# Power.net
KiCad netlist of a schematic drawn in Altium Designer
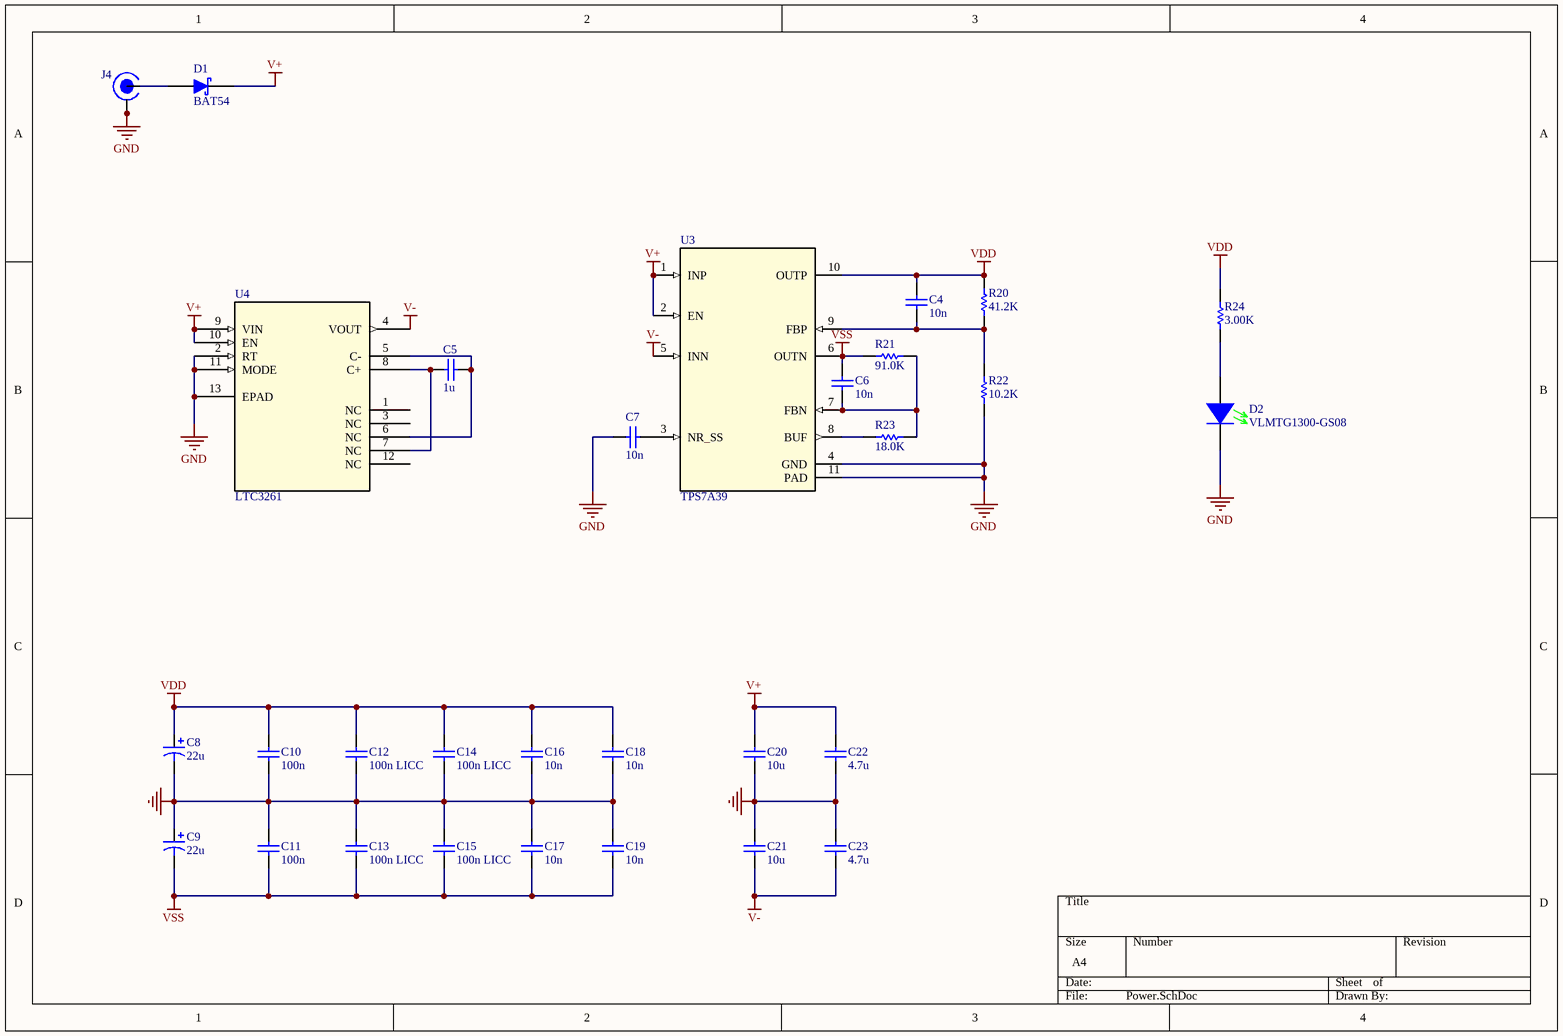
[diagram p0: Power.SchDoc]

(export (version "E")
  (design (tool "Eeschema 10.0.6"))
  (components
    (comp (ref "C4")
      (value "10n")
      (footprint "CAPC0402(1005)50_M")
      (description "CAP CER 10NF±5% 25V C0G 0402")
      (fields
        (field (name "MANUFACTURER") "Murata")
        (field (name "MANUFACTURER PART NUMBER") "GRM1555C1E103JE01D")
      )
      (libsource (lib "Murata GRM 0402") (part "Capacitor_Generic"))
    )
    (comp (ref "C5")
      (value "1u")
      (footprint "CAPC0805(2012)145_M")
      (description "Cap Ceramic 1uF 50V X7R 10% SMD 0805 125C Blister T/R")
      (fields
        (field (name "MANUFACTURER") "Yageo")
        (field (name "MANUFACTURER PART NUMBER") "CC0805KKX7R9BB105")
      )
      (libsource (lib "0805 Caps") (part "CC0805KKX7R9BB105"))
    )
    (comp (ref "C6")
      (value "10n")
      (footprint "CAPC0402(1005)50_M")
      (description "CAP CER 10NF±5% 25V C0G 0402")
      (fields
        (field (name "MANUFACTURER") "Murata")
        (field (name "MANUFACTURER PART NUMBER") "GRM1555C1E103JE01D")
      )
      (libsource (lib "Murata GRM 0402") (part "Capacitor_Generic"))
    )
    (comp (ref "C7")
      (value "10n")
      (footprint "CAPC0402(1005)50_M")
      (description "CAP CER 10NF±5% 25V C0G 0402")
      (fields
        (field (name "MANUFACTURER") "Murata")
        (field (name "MANUFACTURER PART NUMBER") "GRM1555C1E103JE01D")
      )
      (libsource (lib "Murata GRM 0402") (part "Capacitor_Generic"))
    )
    (comp (ref "C8")
      (value "22u")
      (footprint "KEMET D_M")
      (description "CAP TANT 22UF 10% 16V 2917")
      (fields
        (field (name "MANUFACTURER") "KEMET")
        (field (name "MANUFACTURER PART NUMBER") "T491D226K016AT")
      )
      (libsource (lib "Misc Caps") (part "T491D226K016AT"))
    )
    (comp (ref "C9")
      (value "22u")
      (footprint "KEMET D_M")
      (description "CAP TANT 22UF 10% 16V 2917")
      (fields
        (field (name "MANUFACTURER") "KEMET")
        (field (name "MANUFACTURER PART NUMBER") "T491D226K016AT")
      )
      (libsource (lib "Misc Caps") (part "T491D226K016AT"))
    )
    (comp (ref "C10")
      (value "100n")
      (footprint "CAPC0603(1608)100_M")
      (description "CAPACITOR CERAMIC, 0.1UF, 50V, X7R, 10%, 0603")
      (fields
        (field (name "MANUFACTURER") "Yageo")
        (field (name "MANUFACTURER PART NUMBER") "CC0603KRX7R9BB104")
      )
      (libsource (lib "0603 Caps") (part "CC0603KRX7R9BB104"))
    )
    (comp (ref "C11")
      (value "100n")
      (footprint "CAPC0603(1608)100_M")
      (description "CAPACITOR CERAMIC, 0.1UF, 50V, X7R, 10%, 0603")
      (fields
        (field (name "MANUFACTURER") "Yageo")
        (field (name "MANUFACTURER PART NUMBER") "CC0603KRX7R9BB104")
      )
      (libsource (lib "0603 Caps") (part "CC0603KRX7R9BB104"))
    )
    (comp (ref "C12")
      (value "100n LICC")
      (footprint "CAPC0306_M")
      (description "CAP CER 0.1UF 25V X7R 0306")
      (fields
        (field (name "MANUFACTURER") "Taiyo Yuden")
        (field (name "MANUFACTURER PART NUMBER") "TWK107B7104MVHT")
      )
      (libsource (lib "Misc Caps") (part "TWK107B7104MVHT"))
    )
    (comp (ref "C13")
      (value "100n LICC")
      (footprint "CAPC0306_M")
      (description "CAP CER 0.1UF 25V X7R 0306")
      (fields
        (field (name "MANUFACTURER") "Taiyo Yuden")
        (field (name "MANUFACTURER PART NUMBER") "TWK107B7104MVHT")
      )
      (libsource (lib "Misc Caps") (part "TWK107B7104MVHT"))
    )
    (comp (ref "C14")
      (value "100n LICC")
      (footprint "CAPC0306_M")
      (description "CAP CER 0.1UF 25V X7R 0306")
      (fields
        (field (name "MANUFACTURER") "Taiyo Yuden")
        (field (name "MANUFACTURER PART NUMBER") "TWK107B7104MVHT")
      )
      (libsource (lib "Misc Caps") (part "TWK107B7104MVHT"))
    )
    (comp (ref "C15")
      (value "100n LICC")
      (footprint "CAPC0306_M")
      (description "CAP CER 0.1UF 25V X7R 0306")
      (fields
        (field (name "MANUFACTURER") "Taiyo Yuden")
        (field (name "MANUFACTURER PART NUMBER") "TWK107B7104MVHT")
      )
      (libsource (lib "Misc Caps") (part "TWK107B7104MVHT"))
    )
    (comp (ref "C16")
      (value "10n")
      (footprint "CAPC0402(1005)50_M")
      (description "CAP CER 10NF±10% 50V X7R 0402")
      (fields (field (name "PART NUMBER") "GRM155R71H103KA88") (field (name "TOLERANCE") "±10%"))
      (libsource (lib "Murata GRM 0402") (part "Capacitor_Generic"))
    )
    (comp (ref "C17")
      (value "10n")
      (footprint "CAPC0402(1005)50_M")
      (description "CAP CER 10NF±10% 50V X7R 0402")
      (fields (field (name "PART NUMBER") "GRM155R71H103KA88") (field (name "TOLERANCE") "±10%"))
      (libsource (lib "Murata GRM 0402") (part "Capacitor_Generic"))
    )
    (comp (ref "C18")
      (value "10n")
      (footprint "CAPC0402(1005)50_M")
      (description "CAP CER 10NF±10% 50V X7R 0402")
      (fields (field (name "PART NUMBER") "GRM155R71H103KA88") (field (name "TOLERANCE") "±10%"))
      (libsource (lib "Murata GRM 0402") (part "Capacitor_Generic"))
    )
    (comp (ref "C19")
      (value "10n")
      (footprint "CAPC0402(1005)50_M")
      (description "CAP CER 10NF±10% 50V X7R 0402")
      (fields (field (name "PART NUMBER") "GRM155R71H103KA88") (field (name "TOLERANCE") "±10%"))
      (libsource (lib "Murata GRM 0402") (part "Capacitor_Generic"))
    )
    (comp (ref "C20")
      (value "10u")
      (footprint "CAPC1206(3216)170_M")
      (description "CAP CER 10UF 50V X7R 1206")
      (fields
        (field (name "MANUFACTURER") "Samsung")
        (field (name "MANUFACTURER PART NUMBER") "CL31B106KBHNNNE")
      )
      (libsource (lib "Misc Caps") (part "CL31B106KBHNNNE"))
    )
    (comp (ref "C21")
      (value "10u")
      (footprint "CAPC1206(3216)170_M")
      (description "CAP CER 10UF 50V X7R 1206")
      (fields
        (field (name "MANUFACTURER") "Samsung")
        (field (name "MANUFACTURER PART NUMBER") "CL31B106KBHNNNE")
      )
      (libsource (lib "Misc Caps") (part "CL31B106KBHNNNE"))
    )
    (comp (ref "C22")
      (value "4.7u")
      (footprint "CAPC0805(2012)100_M")
      (description "CAP CER 4.7UF 50V X7R 0805")
      (fields
        (field (name "MANUFACTURER") "Murata")
        (field (name "MANUFACTURER PART NUMBER") "GRM21BZ71H475KE15K")
      )
      (libsource (lib "0805 Caps") (part "GRM21BZ71H475KE15K"))
    )
    (comp (ref "C23")
      (value "4.7u")
      (footprint "CAPC0805(2012)100_M")
      (description "CAP CER 4.7UF 50V X7R 0805")
      (fields
        (field (name "MANUFACTURER") "Murata")
        (field (name "MANUFACTURER PART NUMBER") "GRM21BZ71H475KE15K")
      )
      (libsource (lib "0805 Caps") (part "GRM21BZ71H475KE15K"))
    )
    (comp (ref "D1")
      (value "BAT54")
      (footprint "INF-PG-SC59_M")
      (description "DIODE SCHOTTKY 30V 200MA TO236AB")
      (fields
        (field (name "MANUFACTURER") "Nexperia USA")
        (field (name "MANUFACTURER PART NUMBER") "BAT54,215")
      )
      (libsource (lib "Discretes") (part "BAT54"))
    )
    (comp (ref "D2")
      (value "VLMTG1300-GS08")
      (footprint "LED0603(1608)_M")
      (description "LED GREEN 0603 SMD")
      (fields (field (name "MANUFACTURER") "Vishay Semiconductors"))
      (libsource (lib "Discretes") (part "VLMTG1300-GS08"))
    )
    (comp (ref "J4")
      (value "2.1/5.5mm")
      (footprint "CUI PJ-002A")
      (description "CONN PWR JACK 2X5.5MM SOLDER")
      (fields (field (name "MANUFACTURER") "CUI") (field (name "MANUFACTURER PART NUMBER") "PJ-002A"))
      (libsource (lib "Connectors") (part "PJ-002A"))
    )
    (comp (ref "R20")
      (value "41.2K")
      (footprint "RESC0402(1005)_M")
      (description "RES 41.2K OHM 1% 1/16W 0402")
      (fields (field (name "PART NUMBER") "RESC0402-41K2-1pct"))
      (libsource (lib "R0402 - 1pct") (part "Resistor_Generic"))
    )
    (comp (ref "R21")
      (value "91.0K")
      (footprint "RESC0402(1005)_M")
      (description "RES 91.0K OHM 1% 1/16W 0402")
      (fields (field (name "PART NUMBER") "RESC0402-91K0-1pct"))
      (libsource (lib "R0402 - 1pct") (part "Resistor_Generic"))
    )
    (comp (ref "R22")
      (value "10.2K")
      (footprint "RESC0402(1005)_M")
      (description "RES 10.2K OHM 1% 1/16W 0402")
      (fields (field (name "PART NUMBER") "RESC0402-10K2-1pct"))
      (libsource (lib "R0402 - 1pct") (part "Resistor_Generic"))
    )
    (comp (ref "R23")
      (value "18.0K")
      (footprint "RESC0402(1005)_M")
      (description "RES 18.0K OHM 1% 1/16W 0402")
      (fields (field (name "PART NUMBER") "RESC0402-18K0-1pct"))
      (libsource (lib "R0402 - 1pct") (part "Resistor_Generic"))
    )
    (comp (ref "R24")
      (value "3.00K")
      (footprint "RESC0603(1608)_M")
      (description "RES 3.00K OHM 1% 1/10W 0603")
      (fields (field (name "PART NUMBER") "RESC0603-3K00-1pct"))
      (libsource (lib "R0603 - 1pct") (part "Resistor_Generic"))
    )
    (comp (ref "U3")
      (value "TPS7A39")
      (footprint "DSC0010J_NV")
      (description "IC REG LINEAR POS/NEG ADJ 10WSON")
      (fields
        (field (name "MANUFACTURER_PART_NUMBER") "TPS7A3901DSCR")
        (field (name "MANUFACTURER") "Texas Instruments")
        (field (name "COPYRIGHT") "Copyright (C) 2022 Ultra Librarian. All rights reserved.")
      )
      (libsource (lib "IC") (part "TPS7A3901DSCR"))
    )
    (comp (ref "U4")
      (value "LTC3261")
      (footprint "MSOP-12_MSE")
      (description "IC REG CHARG PUMP INV 12MSOP")
      (fields
        (field (name "MANUFACTURER_PART_NUMBER") "ltc3261emse#pbf")
        (field (name "MANUFACTURER") "Analog Devices / Linear Technology")
        (field (name "COPYRIGHT") "Copyright (C) 2022 Ultra Librarian. All rights reserved.")
      )
      (libsource (lib "IC") (part "LTC3261EMSE"))
    )
  )
  (nets
    (net (code "1") (name "GND") (class "Default")
      (node (ref "C10") (pin "2") (pinfunction "2_2") (pintype "passive"))
      (node (ref "C11") (pin "1") (pinfunction "1_1") (pintype "passive"))
      (node (ref "C12") (pin "2") (pinfunction "2_2") (pintype "passive"))
      (node (ref "C13") (pin "1") (pinfunction "1_1") (pintype "passive"))
      (node (ref "C14") (pin "2") (pinfunction "2_2") (pintype "passive"))
      (node (ref "C15") (pin "1") (pinfunction "1_1") (pintype "passive"))
      (node (ref "C16") (pin "2") (pinfunction "2_2") (pintype "passive"))
      (node (ref "C17") (pin "1") (pinfunction "1_1") (pintype "passive"))
      (node (ref "C18") (pin "2") (pinfunction "2_2") (pintype "passive"))
      (node (ref "C19") (pin "1") (pinfunction "1_1") (pintype "passive"))
      (node (ref "C20") (pin "2") (pinfunction "2_2") (pintype "passive"))
      (node (ref "C21") (pin "1") (pinfunction "1_1") (pintype "passive"))
      (node (ref "C22") (pin "2") (pinfunction "2_2") (pintype "passive"))
      (node (ref "C23") (pin "2") (pinfunction "2_2") (pintype "passive"))
      (node (ref "C7") (pin "2") (pinfunction "2_2") (pintype "passive"))
      (node (ref "C8") (pin "2") (pinfunction "2_2") (pintype "passive"))
      (node (ref "C9") (pin "1") (pinfunction "1_1") (pintype "passive"))
      (node (ref "D2") (pin "2") (pinfunction "K_2") (pintype "passive"))
      (node (ref "J4") (pin "2") (pinfunction "2_2") (pintype "passive"))
      (node (ref "J4") (pin "3") (pinfunction "3_3") (pintype "passive"))
      (node (ref "R22") (pin "2") (pinfunction "2_2") (pintype "passive"))
      (node (ref "U3") (pin "11") (pinfunction "PAD_11") (pintype "power_in"))
      (node (ref "U3") (pin "4") (pinfunction "GND_4") (pintype "power_in"))
      (node (ref "U4") (pin "11") (pinfunction "MODE_11") (pintype "input"))
      (node (ref "U4") (pin "13") (pinfunction "EPAD_13") (pintype "passive"))
      (node (ref "U4") (pin "2") (pinfunction "RT_2") (pintype "input"))
    )
    (net (code "2") (name "Net-(D1-A)") (class "Default")
      (node (ref "D1") (pin "1") (pinfunction "A_1") (pintype "passive"))
      (node (ref "J4") (pin "1") (pinfunction "1_1") (pintype "passive"))
    )
    (net (code "3") (name "Net-(D2-A)") (class "Default")
      (node (ref "D2") (pin "1") (pinfunction "A_1") (pintype "passive"))
      (node (ref "R24") (pin "2") (pinfunction "2_2") (pintype "passive"))
    )
    (net (code "4") (name "Net-(U3-BUF)") (class "Default")
      (node (ref "R23") (pin "2") (pinfunction "2_2") (pintype "passive"))
      (node (ref "U3") (pin "8") (pinfunction "BUF_8") (pintype "output"))
    )
    (net (code "5") (name "Net-(U3-FBN)") (class "Default")
      (node (ref "C6") (pin "1") (pinfunction "1_1") (pintype "passive"))
      (node (ref "R21") (pin "1") (pinfunction "1_1") (pintype "passive"))
      (node (ref "R23") (pin "1") (pinfunction "1_1") (pintype "passive"))
      (node (ref "U3") (pin "7") (pinfunction "FBN_7") (pintype "input"))
    )
    (net (code "6") (name "Net-(U3-FBP)") (class "Default")
      (node (ref "C4") (pin "1") (pinfunction "1_1") (pintype "passive"))
      (node (ref "R20") (pin "2") (pinfunction "2_2") (pintype "passive"))
      (node (ref "R22") (pin "1") (pinfunction "1_1") (pintype "passive"))
      (node (ref "U3") (pin "9") (pinfunction "FBP_9") (pintype "input"))
    )
    (net (code "7") (name "Net-(U3-NR_SS)") (class "Default")
      (node (ref "C7") (pin "1") (pinfunction "1_1") (pintype "passive"))
      (node (ref "U3") (pin "3") (pinfunction "NR_SS_3") (pintype "input"))
    )
    (net (code "8") (name "Net-(U4-C+)") (class "Default")
      (node (ref "C5") (pin "1") (pinfunction "1_1") (pintype "passive"))
      (node (ref "U4") (pin "7") (pinfunction "NC_7") (pintype "passive"))
      (node (ref "U4") (pin "8") (pinfunction "C+_8") (pintype "passive"))
    )
    (net (code "9") (name "Net-(U4-C-)") (class "Default")
      (node (ref "C5") (pin "2") (pinfunction "2_2") (pintype "passive"))
      (node (ref "U4") (pin "5") (pinfunction "C-_5") (pintype "passive"))
      (node (ref "U4") (pin "6") (pinfunction "NC_6") (pintype "passive"))
    )
    (net (code "10") (name "V+") (class "Default")
      (node (ref "C20") (pin "1") (pinfunction "1_1") (pintype "passive"))
      (node (ref "C22") (pin "1") (pinfunction "1_1") (pintype "passive"))
      (node (ref "D1") (pin "3") (pinfunction "K_3") (pintype "passive"))
      (node (ref "U3") (pin "1") (pinfunction "INP_1") (pintype "input"))
      (node (ref "U3") (pin "2") (pinfunction "EN_2") (pintype "input"))
      (node (ref "U4") (pin "10") (pinfunction "EN_10") (pintype "input"))
      (node (ref "U4") (pin "9") (pinfunction "VIN_9") (pintype "input"))
    )
    (net (code "11") (name "V-") (class "Default")
      (node (ref "C21") (pin "2") (pinfunction "2_2") (pintype "passive"))
      (node (ref "C23") (pin "1") (pinfunction "1_1") (pintype "passive"))
      (node (ref "U3") (pin "5") (pinfunction "INN_5") (pintype "input"))
      (node (ref "U4") (pin "4") (pinfunction "VOUT_4") (pintype "output"))
    )
    (net (code "12") (name "VDD") (class "Default")
      (node (ref "C10") (pin "1") (pinfunction "1_1") (pintype "passive"))
      (node (ref "C12") (pin "1") (pinfunction "1_1") (pintype "passive"))
      (node (ref "C14") (pin "1") (pinfunction "1_1") (pintype "passive"))
      (node (ref "C16") (pin "1") (pinfunction "1_1") (pintype "passive"))
      (node (ref "C18") (pin "1") (pinfunction "1_1") (pintype "passive"))
      (node (ref "C4") (pin "2") (pinfunction "2_2") (pintype "passive"))
      (node (ref "C8") (pin "1") (pinfunction "1_1") (pintype "passive"))
      (node (ref "R20") (pin "1") (pinfunction "1_1") (pintype "passive"))
      (node (ref "R24") (pin "1") (pinfunction "1_1") (pintype "passive"))
      (node (ref "U3") (pin "10") (pinfunction "OUTP_10") (pintype "power_in"))
    )
    (net (code "13") (name "VSS") (class "Default")
      (node (ref "C11") (pin "2") (pinfunction "2_2") (pintype "passive"))
      (node (ref "C13") (pin "2") (pinfunction "2_2") (pintype "passive"))
      (node (ref "C15") (pin "2") (pinfunction "2_2") (pintype "passive"))
      (node (ref "C17") (pin "2") (pinfunction "2_2") (pintype "passive"))
      (node (ref "C19") (pin "2") (pinfunction "2_2") (pintype "passive"))
      (node (ref "C6") (pin "2") (pinfunction "2_2") (pintype "passive"))
      (node (ref "C9") (pin "2") (pinfunction "2_2") (pintype "passive"))
      (node (ref "R21") (pin "2") (pinfunction "2_2") (pintype "passive"))
      (node (ref "U3") (pin "6") (pinfunction "OUTN_6") (pintype "power_in"))
    )
    (net (code "14") (name "unconnected-(U4-NC-Pad1)") (class "Default")
      (node (ref "U4") (pin "1") (pinfunction "NC_1") (pintype "passive"))
    )
    (net (code "15") (name "unconnected-(U4-NC-Pad3)") (class "Default")
      (node (ref "U4") (pin "3") (pinfunction "NC_3") (pintype "passive"))
    )
    (net (code "16") (name "unconnected-(U4-NC-Pad12)") (class "Default")
      (node (ref "U4") (pin "12") (pinfunction "NC_12") (pintype "passive"))
    )
  )
)
